# untitled2.net
KiCad netlist of a schematic drawn in EAGLE
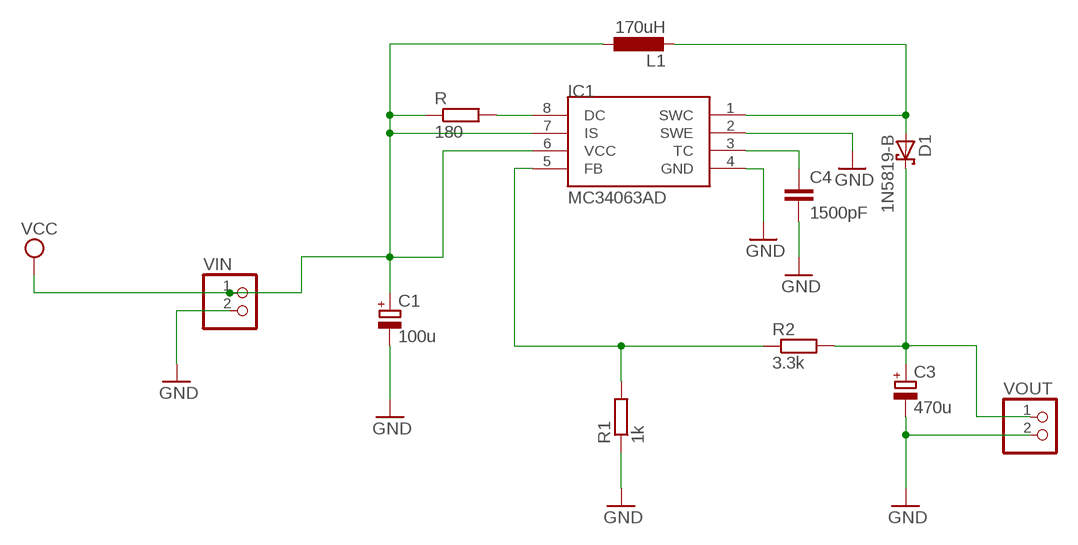
[diagram p0: schematic, sheet 1]

(export (version "E")
  (design (tool "Eeschema 10.0.6"))
  (components
    (comp (ref "C1")
      (value "100u")
      (footprint "eagle-import:E2,5-6E")
      (libsource (lib "eagle-import") (part "CPOL-EUE2,5-6E"))
    )
    (comp (ref "C3")
      (value "470u")
      (footprint "eagle-import:E5-10,5")
      (libsource (lib "eagle-import") (part "CPOL-EUE5-10.5"))
    )
    (comp (ref "C4")
      (value "1500pF")
      (footprint "eagle-import:C1206")
      (libsource (lib "eagle-import") (part "C-EUC1206"))
    )
    (comp (ref "D1")
      (value "1N5819-B")
      (footprint "eagle-import:DO41-7.6")
      (libsource (lib "eagle-import") (part "1N5819-B"))
    )
    (comp (ref "IC1")
      (value "MC34063AD")
      (footprint "eagle-import:SOIC8")
      (libsource (lib "eagle-import") (part "MC34063AD"))
    )
    (comp (ref "L1")
      (value "170uH")
      (footprint "eagle-import:0204_5")
      (libsource (lib "eagle-import") (part "L-EU0204/5"))
    )
    (comp (ref "R")
      (value "180")
      (footprint "eagle-import:R0805W")
      (libsource (lib "eagle-import") (part "R-EU_R0805W"))
    )
    (comp (ref "R1")
      (value "1k")
      (footprint "eagle-import:R1206W")
      (libsource (lib "eagle-import") (part "R-EU_R1206W"))
    )
    (comp (ref "R2")
      (value "3.3k")
      (footprint "eagle-import:R1206W")
      (libsource (lib "eagle-import") (part "R-EU_R1206W"))
    )
    (comp (ref "VIN")
      (value "PINHD-1X2")
      (footprint "eagle-import:1X02")
      (libsource (lib "eagle-import") (part "PINHD-1X2"))
    )
    (comp (ref "VOUT")
      (value "PINHD-1X2")
      (footprint "eagle-import:1X02")
      (libsource (lib "eagle-import") (part "PINHD-1X2"))
    )
  )
  (nets
    (net (code "1") (name "GND") (class "Default")
      (node (ref "C1") (pin "-") (pinfunction "-_-") (pintype "passive"))
      (node (ref "C3") (pin "-") (pinfunction "-_-") (pintype "passive"))
      (node (ref "C4") (pin "2") (pinfunction "2_2") (pintype "passive"))
      (node (ref "IC1") (pin "2") (pinfunction "SWE_2") (pintype "passive"))
      (node (ref "IC1") (pin "4") (pinfunction "GND_4") (pintype "passive"))
      (node (ref "R1") (pin "1") (pinfunction "1_1") (pintype "passive"))
      (node (ref "VIN") (pin "2") (pinfunction "2_2") (pintype "passive"))
      (node (ref "VOUT") (pin "2") (pinfunction "2_2") (pintype "passive"))
    )
    (net (code "2") (name "Net-(C3-Pad+)") (class "Default")
      (node (ref "C3") (pin "+") (pinfunction "+_+") (pintype "passive"))
      (node (ref "D1") (pin "C") (pinfunction "C_C") (pintype "passive"))
      (node (ref "R2") (pin "2") (pinfunction "2_2") (pintype "passive"))
      (node (ref "VOUT") (pin "1") (pinfunction "1_1") (pintype "passive"))
    )
    (net (code "3") (name "Net-(IC1-DC)") (class "Default")
      (node (ref "IC1") (pin "8") (pinfunction "DC_8") (pintype "passive"))
      (node (ref "R") (pin "2") (pinfunction "2_2") (pintype "passive"))
    )
    (net (code "4") (name "Net-(IC1-FB)") (class "Default")
      (node (ref "IC1") (pin "5") (pinfunction "FB_5") (pintype "passive"))
      (node (ref "R1") (pin "2") (pinfunction "2_2") (pintype "passive"))
      (node (ref "R2") (pin "1") (pinfunction "1_1") (pintype "passive"))
    )
    (net (code "5") (name "Net-(IC1-SWC)") (class "Default")
      (node (ref "D1") (pin "A") (pinfunction "A_A") (pintype "passive"))
      (node (ref "IC1") (pin "1") (pinfunction "SWC_1") (pintype "passive"))
      (node (ref "L1") (pin "2") (pinfunction "2_2") (pintype "passive"))
    )
    (net (code "6") (name "Net-(IC1-TC)") (class "Default")
      (node (ref "C4") (pin "1") (pinfunction "1_1") (pintype "passive"))
      (node (ref "IC1") (pin "3") (pinfunction "TC_3") (pintype "passive"))
    )
    (net (code "7") (name "VCC") (class "Default")
      (node (ref "C1") (pin "+") (pinfunction "+_+") (pintype "passive"))
      (node (ref "IC1") (pin "6") (pinfunction "VCC_6") (pintype "passive"))
      (node (ref "IC1") (pin "7") (pinfunction "IS_7") (pintype "passive"))
      (node (ref "L1") (pin "1") (pinfunction "1_1") (pintype "passive"))
      (node (ref "R") (pin "1") (pinfunction "1_1") (pintype "passive"))
      (node (ref "VIN") (pin "1") (pinfunction "1_1") (pintype "passive"))
    )
  )
)
